# usb_power.net
KiCad netlist of a schematic drawn in EAGLE
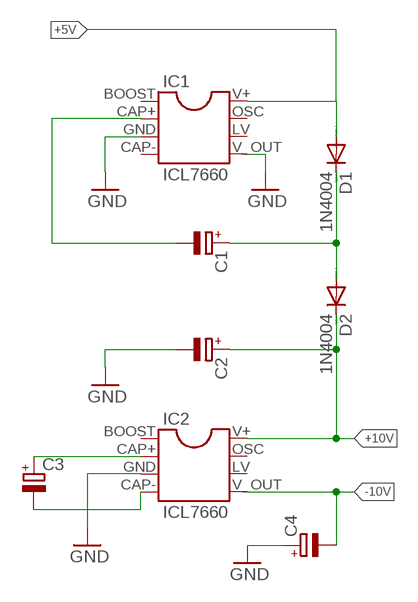
[diagram p0: schematic, sheet 1]

(export (version "E")
  (design (tool "Eeschema 10.0.6"))
  (components
    (comp (ref "C1")
      (value "CPOL-EUE2-4")
      (footprint "eagle-import:E2-4")
      (libsource (lib "eagle-import") (part "CPOL-EUE2-4"))
    )
    (comp (ref "C2")
      (value "CPOL-EUE2-4")
      (footprint "eagle-import:E2-4")
      (libsource (lib "eagle-import") (part "CPOL-EUE2-4"))
    )
    (comp (ref "C3")
      (value "CPOL-EUE2-4")
      (footprint "eagle-import:E2-4")
      (libsource (lib "eagle-import") (part "CPOL-EUE2-4"))
    )
    (comp (ref "C4")
      (value "CPOL-EUE2-4")
      (footprint "eagle-import:E2-4")
      (libsource (lib "eagle-import") (part "CPOL-EUE2-4"))
    )
    (comp (ref "D1")
      (value "1N4004")
      (footprint "eagle-import:DO41-10")
      (libsource (lib "eagle-import") (part "1N4004"))
    )
    (comp (ref "D2")
      (value "1N4004")
      (footprint "eagle-import:DO41-10")
      (libsource (lib "eagle-import") (part "1N4004"))
    )
    (comp (ref "IC1")
      (value "ICL7660")
      (footprint "eagle-import:DIL08")
      (libsource (lib "eagle-import") (part "DIL8"))
    )
    (comp (ref "IC2")
      (value "ICL7660")
      (footprint "eagle-import:DIL08")
      (libsource (lib "eagle-import") (part "DIL8"))
    )
  )
  (nets
    (net (code "1") (name "+5V") (class "Default")
      (node (ref "D1") (pin "A") (pinfunction "A_A") (pintype "passive"))
      (node (ref "IC1") (pin "V+") (pinfunction "8_V+") (pintype "passive"))
    )
    (net (code "2") (name "+10V") (class "Default")
      (node (ref "C2") (pin "+") (pinfunction "+_+") (pintype "passive"))
      (node (ref "D2") (pin "C") (pinfunction "C_C") (pintype "passive"))
      (node (ref "IC2") (pin "V+") (pinfunction "8_V+") (pintype "passive"))
    )
    (net (code "3") (name "-10V") (class "Default")
      (node (ref "C4") (pin "-") (pinfunction "-_-") (pintype "passive"))
      (node (ref "IC2") (pin "V_OUT") (pinfunction "5_V_OUT") (pintype "passive"))
    )
    (net (code "4") (name "GND") (class "Default")
      (node (ref "C2") (pin "-") (pinfunction "-_-") (pintype "passive"))
      (node (ref "C4") (pin "+") (pinfunction "+_+") (pintype "passive"))
      (node (ref "IC1") (pin "GND") (pinfunction "3_GND") (pintype "passive"))
      (node (ref "IC1") (pin "V_OUT") (pinfunction "5_V_OUT") (pintype "passive"))
      (node (ref "IC2") (pin "GND") (pinfunction "3_GND") (pintype "passive"))
    )
    (net (code "5") (name "Net-(C1-Pad+)") (class "Default")
      (node (ref "C1") (pin "+") (pinfunction "+_+") (pintype "passive"))
      (node (ref "D1") (pin "C") (pinfunction "C_C") (pintype "passive"))
      (node (ref "D2") (pin "A") (pinfunction "A_A") (pintype "passive"))
    )
    (net (code "6") (name "Net-(IC1-2)") (class "Default")
      (node (ref "C1") (pin "-") (pinfunction "-_-") (pintype "passive"))
      (node (ref "IC1") (pin "CAP+") (pinfunction "2_CAP+") (pintype "passive"))
    )
    (net (code "7") (name "Net-(IC2-2)") (class "Default")
      (node (ref "C3") (pin "+") (pinfunction "+_+") (pintype "passive"))
      (node (ref "IC2") (pin "CAP+") (pinfunction "2_CAP+") (pintype "passive"))
    )
    (net (code "8") (name "Net-(IC2-4)") (class "Default")
      (node (ref "C3") (pin "-") (pinfunction "-_-") (pintype "passive"))
      (node (ref "IC2") (pin "CAP-") (pinfunction "4_CAP-") (pintype "passive"))
    )
    (net (code "9") (name "unconnected-(IC1-1-PadBOOST)") (class "Default")
      (node (ref "IC1") (pin "BOOST") (pinfunction "1_BOOST") (pintype "passive"))
    )
    (net (code "10") (name "unconnected-(IC1-4-PadCAP-)") (class "Default")
      (node (ref "IC1") (pin "CAP-") (pinfunction "4_CAP-") (pintype "passive"))
    )
    (net (code "11") (name "unconnected-(IC1-6-PadLV)") (class "Default")
      (node (ref "IC1") (pin "LV") (pinfunction "6_LV") (pintype "passive"))
    )
    (net (code "12") (name "unconnected-(IC1-7-PadOSC)") (class "Default")
      (node (ref "IC1") (pin "OSC") (pinfunction "7_OSC") (pintype "passive"))
    )
    (net (code "13") (name "unconnected-(IC2-1-PadBOOST)") (class "Default")
      (node (ref "IC2") (pin "BOOST") (pinfunction "1_BOOST") (pintype "passive"))
    )
    (net (code "14") (name "unconnected-(IC2-6-PadLV)") (class "Default")
      (node (ref "IC2") (pin "LV") (pinfunction "6_LV") (pintype "passive"))
    )
    (net (code "15") (name "unconnected-(IC2-7-PadOSC)") (class "Default")
      (node (ref "IC2") (pin "OSC") (pinfunction "7_OSC") (pintype "passive"))
    )
  )
)
